# harp_behavior_poke_port_breakout_v2_1.net
KiCad netlist of a schematic drawn in EAGLE
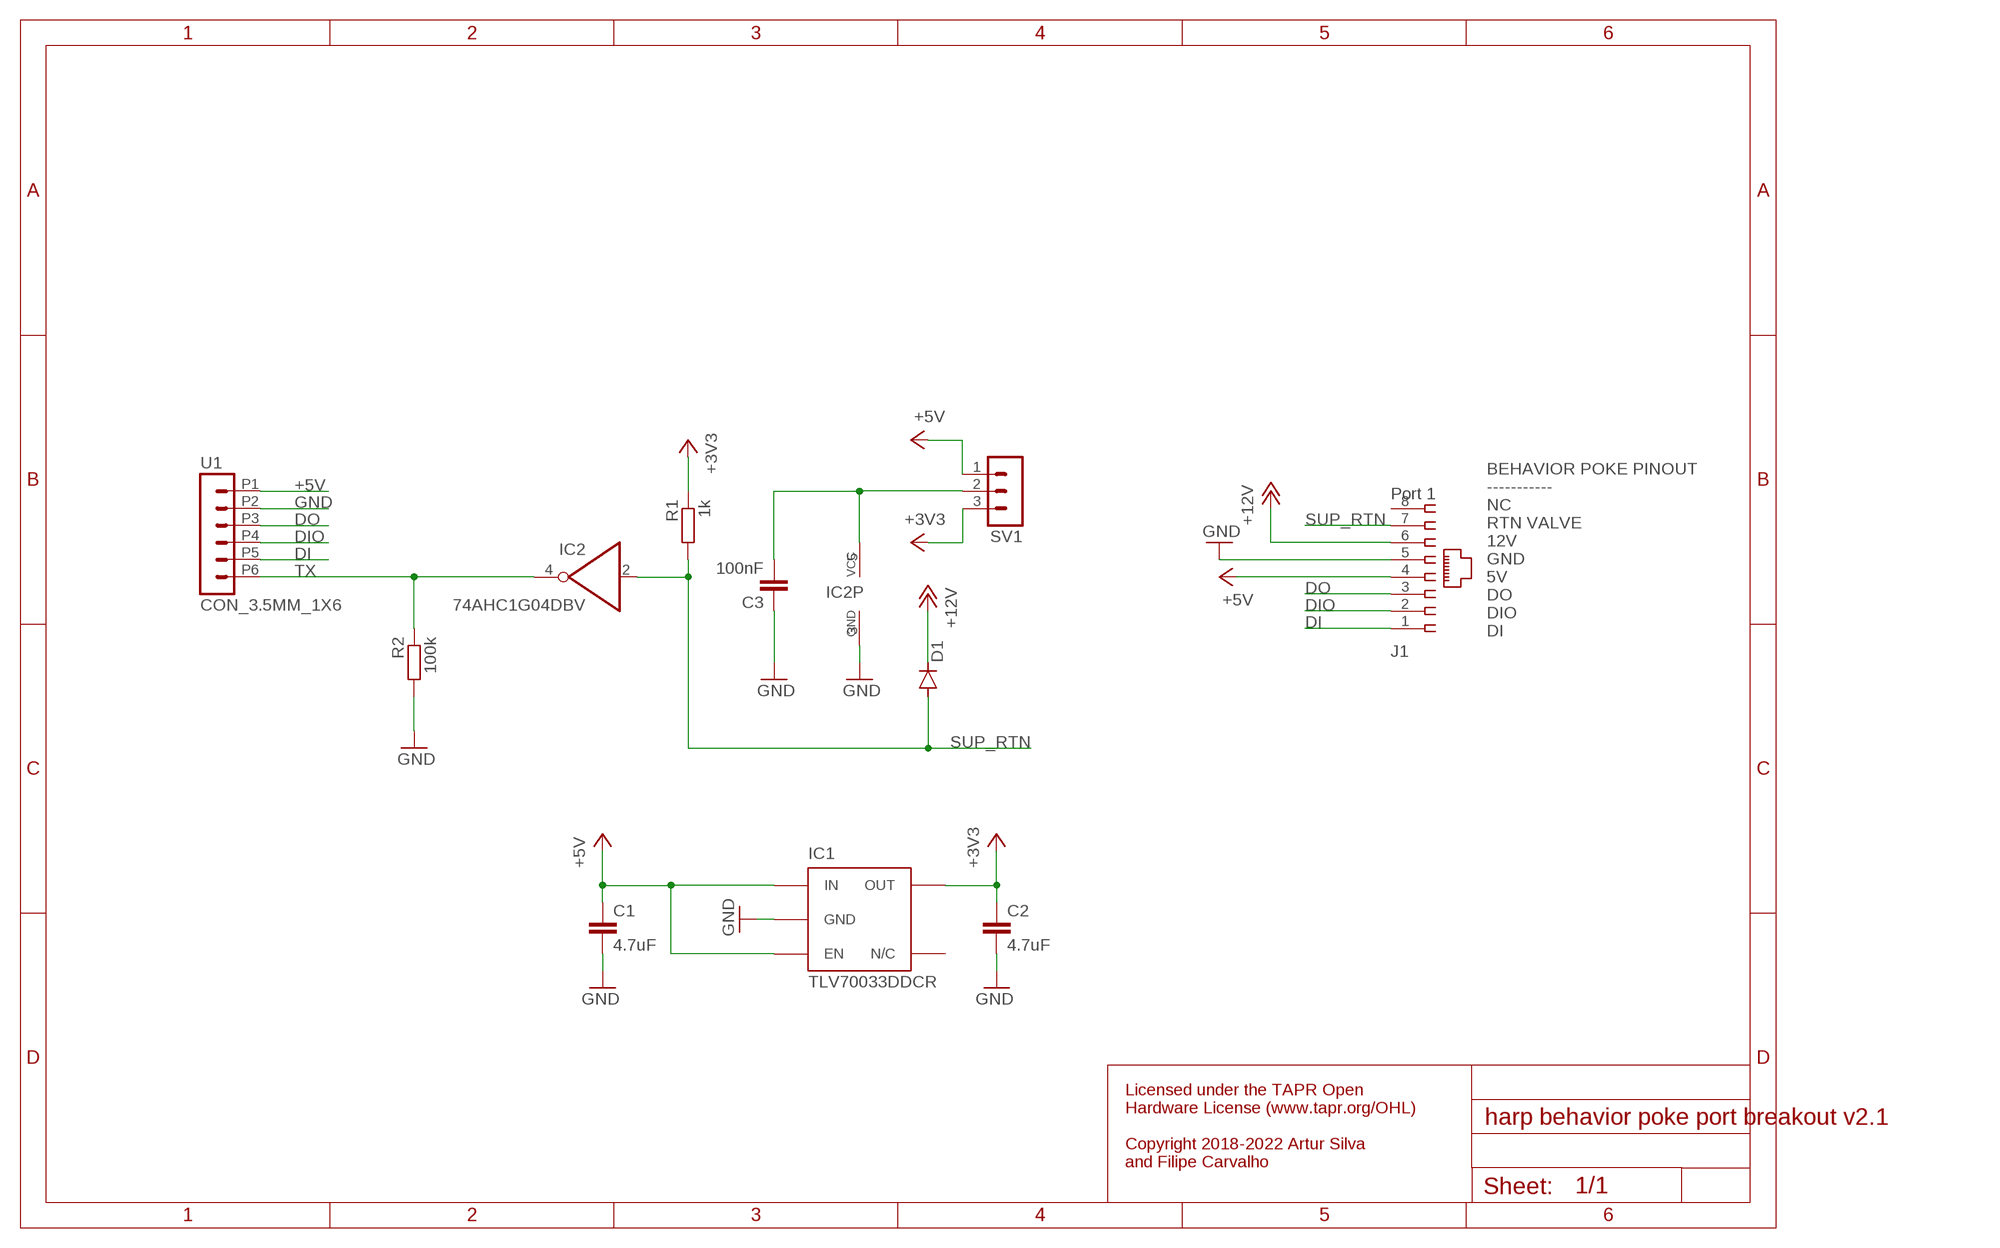
[diagram p0: schematic, sheet 1]

(export (version "E")
  (design (tool "Eeschema 10.0.6"))
  (components
    (comp (ref "C1")
      (value "4.7uF")
      (footprint "eagle-import:C0603")
      (libsource (lib "eagle-import") (part "C-EUC0603"))
    )
    (comp (ref "C2")
      (value "4.7uF")
      (footprint "eagle-import:C0603")
      (libsource (lib "eagle-import") (part "C-EUC0603"))
    )
    (comp (ref "C3")
      (value "100nF")
      (footprint "eagle-import:C0402")
      (libsource (lib "eagle-import") (part "C-EUC0402"))
    )
    (comp (ref "D1")
      (value "DIODE")
      (footprint "eagle-import:SOD-323-DIODE")
      (libsource (lib "eagle-import") (part "DIODE"))
    )
    (comp (ref "IC1")
      (value "TLV70033DDCR")
      (footprint "eagle-import:TSOT23-5")
      (libsource (lib "eagle-import") (part "TLV700XX"))
    )
    (comp (ref "IC2")
      (value "74AHC1G04DBV")
      (footprint "eagle-import:SOT23-5")
      (libsource (lib "eagle-import") (part "741G04DBVAHC"))
    )
    (comp (ref "J1")
      (value "Port 1")
      (footprint "eagle-import:520426-4")
      (libsource (lib "eagle-import") (part "520426-4"))
    )
    (comp (ref "R1")
      (value "1k")
      (footprint "eagle-import:R0402")
      (libsource (lib "eagle-import") (part "R-EU_R0402"))
    )
    (comp (ref "R2")
      (value "100k")
      (footprint "eagle-import:R0402")
      (libsource (lib "eagle-import") (part "R-EU_R0402"))
    )
    (comp (ref "SV1")
      (value "MA03-1")
      (footprint "eagle-import:MA03-1")
      (libsource (lib "eagle-import") (part "MA03-1"))
    )
    (comp (ref "U1")
      (value "CON_3.5MM_1X6")
      (footprint "eagle-import:CON_3.5MM_1X6")
      (libsource (lib "eagle-import") (part "CON_3.5MM_1X6"))
    )
  )
  (nets
    (net (code "1") (name "+3V3") (class "Default")
      (node (ref "C2") (pin "1") (pinfunction "1_1") (pintype "passive"))
      (node (ref "IC1") (pin "5") (pinfunction "OUT_5") (pintype "bidirectional"))
      (node (ref "R1") (pin "1") (pinfunction "1_1") (pintype "passive"))
      (node (ref "SV1") (pin "3") (pinfunction "3_3") (pintype "passive"))
    )
    (net (code "2") (name "+5V") (class "Default")
      (node (ref "C1") (pin "1") (pinfunction "1_1") (pintype "passive"))
      (node (ref "IC1") (pin "1") (pinfunction "IN_1") (pintype "bidirectional"))
      (node (ref "IC1") (pin "3") (pinfunction "EN_3") (pintype "bidirectional"))
      (node (ref "J1") (pin "4") (pinfunction "4_4") (pintype "passive"))
      (node (ref "SV1") (pin "1") (pinfunction "1_1") (pintype "passive"))
      (node (ref "U1") (pin "P1") (pinfunction "1_P1") (pintype "passive"))
    )
    (net (code "3") (name "+12V") (class "Default")
      (node (ref "D1") (pin "C") (pinfunction "C_C") (pintype "passive"))
      (node (ref "J1") (pin "6") (pinfunction "6_6") (pintype "passive"))
    )
    (net (code "4") (name "/DI") (class "Default")
      (node (ref "J1") (pin "1") (pinfunction "1_1") (pintype "passive"))
      (node (ref "U1") (pin "P5") (pinfunction "5_P5") (pintype "passive"))
    )
    (net (code "5") (name "/DIO") (class "Default")
      (node (ref "J1") (pin "2") (pinfunction "2_2") (pintype "passive"))
      (node (ref "U1") (pin "P4") (pinfunction "4_P4") (pintype "passive"))
    )
    (net (code "6") (name "/DO") (class "Default")
      (node (ref "J1") (pin "3") (pinfunction "3_3") (pintype "passive"))
      (node (ref "U1") (pin "P3") (pinfunction "3_P3") (pintype "passive"))
    )
    (net (code "7") (name "/SUP_RTN") (class "Default")
      (node (ref "D1") (pin "A") (pinfunction "A_A") (pintype "passive"))
      (node (ref "IC2") (pin "2") (pinfunction "I_2") (pintype "input"))
      (node (ref "J1") (pin "7") (pinfunction "7_7") (pintype "passive"))
      (node (ref "R1") (pin "2") (pinfunction "2_2") (pintype "passive"))
    )
    (net (code "8") (name "/TX") (class "Default")
      (node (ref "IC2") (pin "4") (pinfunction "O_4") (pintype "output"))
      (node (ref "R2") (pin "1") (pinfunction "1_1") (pintype "passive"))
      (node (ref "U1") (pin "P6") (pinfunction "6_P6") (pintype "passive"))
    )
    (net (code "9") (name "GND") (class "Default")
      (node (ref "C1") (pin "2") (pinfunction "2_2") (pintype "passive"))
      (node (ref "C2") (pin "2") (pinfunction "2_2") (pintype "passive"))
      (node (ref "C3") (pin "1") (pinfunction "1_1") (pintype "passive"))
      (node (ref "IC1") (pin "2") (pinfunction "GND_2") (pintype "bidirectional"))
      (node (ref "IC2") (pin "3") (pinfunction "GND_3") (pintype "power_in"))
      (node (ref "J1") (pin "5") (pinfunction "5_5") (pintype "passive"))
      (node (ref "R2") (pin "2") (pinfunction "2_2") (pintype "passive"))
      (node (ref "U1") (pin "P2") (pinfunction "2_P2") (pintype "passive"))
    )
    (net (code "10") (name "Net-(IC2B-VCC)") (class "Default")
      (node (ref "C3") (pin "2") (pinfunction "2_2") (pintype "passive"))
      (node (ref "IC2") (pin "5") (pinfunction "VCC_5") (pintype "power_in"))
      (node (ref "SV1") (pin "2") (pinfunction "2_2") (pintype "passive"))
    )
    (net (code "11") (name "unconnected-(IC1-N{slash}C-Pad4)") (class "Default")
      (node (ref "IC1") (pin "4") (pinfunction "N/C_4") (pintype "bidirectional"))
    )
    (net (code "12") (name "unconnected-(J1-Pad8)") (class "Default")
      (node (ref "J1") (pin "8") (pinfunction "8_8") (pintype "passive"))
    )
  )
)
